# SCH_675.net
KiCad netlist of a schematic drawn in Altium Designer
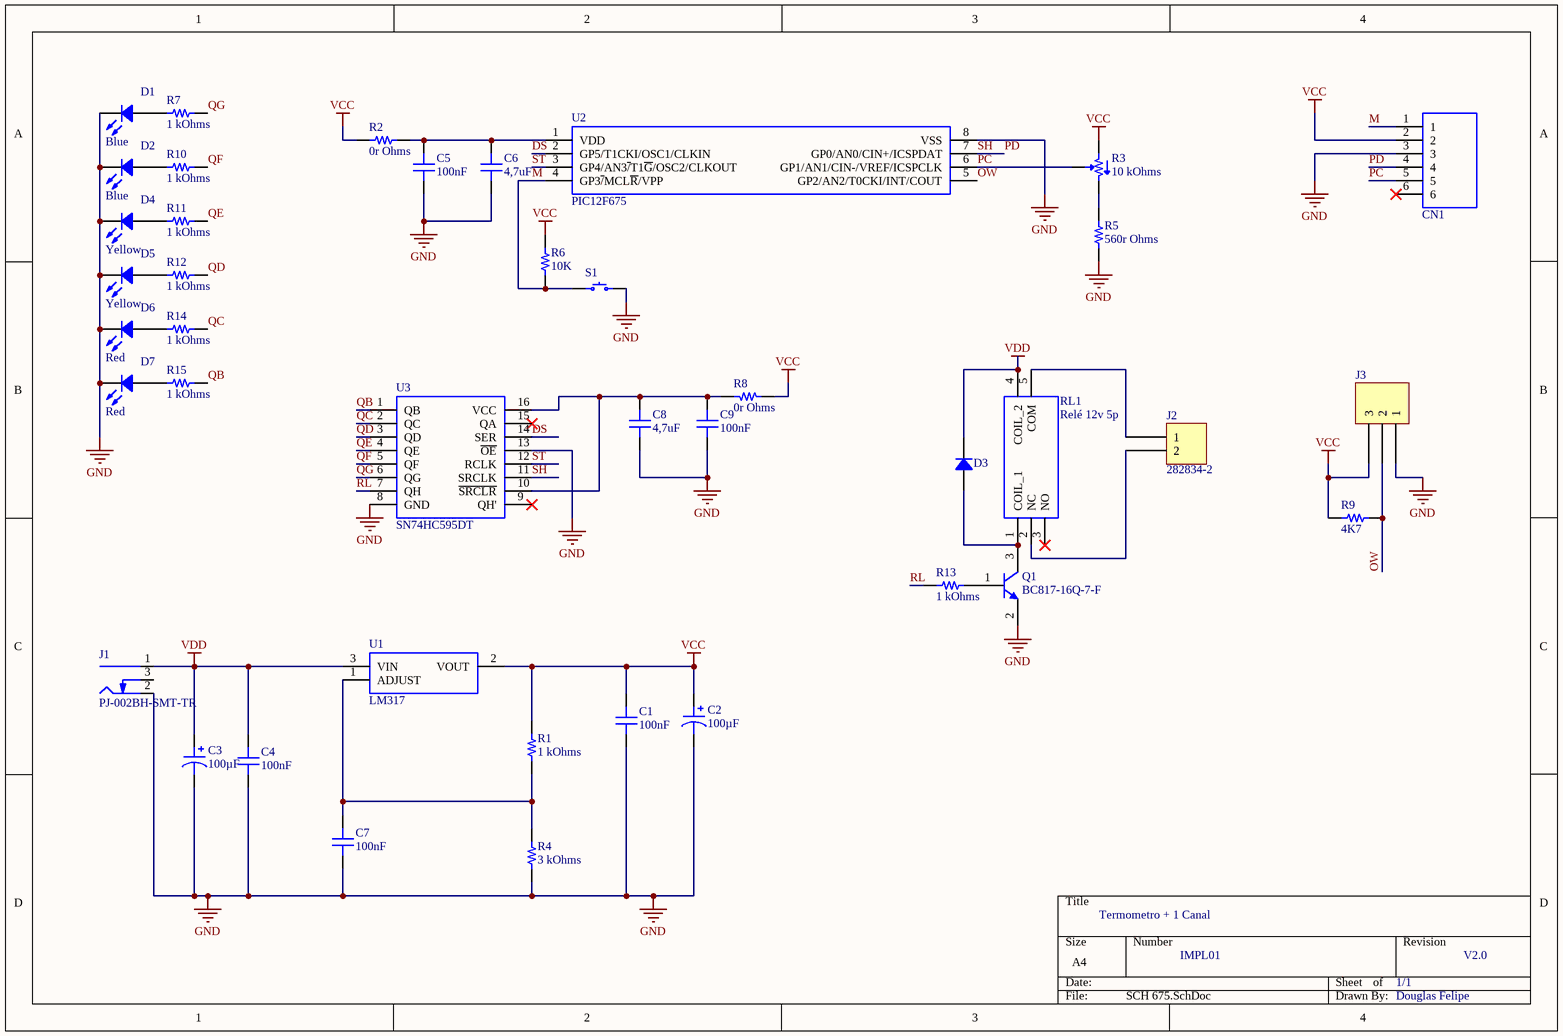
[diagram p0: SCH 675.SchDoc]

(export (version "E")
  (design (tool "Eeschema 10.0.6"))
  (components
    (comp (ref "C1")
      (value "100nF")
      (footprint "CAP 0805_2012")
      (description "CAP CER 100PF 200V C0G/NP0 0805")
      (fields (field (name "PART NUMBER") "08052A101JAT2A") (field (name "MANUFACTURER") "AVX Corporation"))
      (libsource (lib "Celestial Altium Library - altium_library") (part "Capacitor"))
    )
    (comp (ref "C2")
      (value "100µF")
      (footprint "CAP ALSMD 8.3MM H10.5MM")
      (description "CAP ALUM 22UF 20% 100V SMD")
      (fields (field (name "PART NUMBER") "100SEV22M8X10.5") (field (name "MANUFACTURER") "Rubycon"))
      (libsource (lib "Celestial Altium Library - altium_library") (part "Polarised Capacitor"))
    )
    (comp (ref "C3")
      (value "100µF")
      (footprint "CAP ALSMD 8.3MM H10.5MM")
      (description "CAP ALUM 22UF 20% 100V SMD")
      (fields (field (name "PART NUMBER") "100SEV22M8X10.5") (field (name "MANUFACTURER") "Rubycon"))
      (libsource (lib "Celestial Altium Library - altium_library") (part "Polarised Capacitor"))
    )
    (comp (ref "C4")
      (value "100nF")
      (footprint "CAP 0805_2012")
      (description "CAP CER 100PF 200V C0G/NP0 0805")
      (fields (field (name "PART NUMBER") "08052A101JAT2A") (field (name "MANUFACTURER") "AVX Corporation"))
      (libsource (lib "Celestial Altium Library - altium_library") (part "Capacitor"))
    )
    (comp (ref "C5")
      (value "100nF")
      (footprint "CAP 0805_2012")
      (description "CAP CER 100PF 200V C0G/NP0 0805")
      (fields (field (name "PART NUMBER") "08052A101JAT2A") (field (name "MANUFACTURER") "AVX Corporation"))
      (libsource (lib "Celestial Altium Library - altium_library") (part "Capacitor"))
    )
    (comp (ref "C6")
      (value "4,7uF")
      (footprint "CAP 0805_2012")
      (description "CAP CER 100PF 200V C0G/NP0 0805")
      (fields (field (name "PART NUMBER") "08052A101JAT2A") (field (name "MANUFACTURER") "AVX Corporation"))
      (libsource (lib "Celestial Altium Library - altium_library") (part "Capacitor"))
    )
    (comp (ref "C7")
      (value "100nF")
      (footprint "CAP 0805_2012")
      (description "CAP CER 100PF 200V C0G/NP0 0805")
      (fields (field (name "PART NUMBER") "08052A101JAT2A") (field (name "MANUFACTURER") "AVX Corporation"))
      (libsource (lib "Celestial Altium Library - altium_library") (part "Capacitor"))
    )
    (comp (ref "C8")
      (value "4,7uF")
      (footprint "CAP 0805_2012")
      (description "CAP CER 100PF 200V C0G/NP0 0805")
      (fields (field (name "PART NUMBER") "08052A101JAT2A") (field (name "MANUFACTURER") "AVX Corporation"))
      (libsource (lib "Celestial Altium Library - altium_library") (part "Capacitor"))
    )
    (comp (ref "C9")
      (value "100nF")
      (footprint "CAP 0805_2012")
      (description "CAP CER 100PF 200V C0G/NP0 0805")
      (fields (field (name "PART NUMBER") "08052A101JAT2A") (field (name "MANUFACTURER") "AVX Corporation"))
      (libsource (lib "Celestial Altium Library - altium_library") (part "Capacitor"))
    )
    (comp (ref "CN1")
      (value "KK 6vias")
      (footprint "KK6")
      (libsource (lib "Meus Components") (part "KK 6vias"))
    )
    (comp (ref "D1")
      (value "Blue")
      (footprint "LED 0805_2012 BLUE")
      (description "2.0(L)X1.3(W)X0.8(H) MM")
      (fields
        (field (name "PART NUMBER") "B1701NB--20D000114U1930")
        (field (name "MANUFACTURER") "Harvatek Corporation")
      )
      (libsource (lib "Celestial Altium Library - altium_library") (part "LED"))
    )
    (comp (ref "D2")
      (value "Blue")
      (footprint "LED 0805_2012 BLUE")
      (description "2.0(L)X1.3(W)X0.8(H) MM")
      (fields
        (field (name "PART NUMBER") "B1701NB--20D000114U1930")
        (field (name "MANUFACTURER") "Harvatek Corporation")
      )
      (libsource (lib "Celestial Altium Library - altium_library") (part "LED"))
    )
    (comp (ref "D3")
      (value "1N4148W-TP")
      (footprint "SOD-123")
      (description "DIODE GEN PURP 100V 150MA SOD123")
      (fields (field (name "MANUFACTURER") "Micro Commercial Co"))
      (libsource (lib "Celestial Altium Library - altium_library") (part "Diode"))
    )
    (comp (ref "D4")
      (value "Yellow")
      (footprint "LED 0805_2012 YELLOW")
      (description "LED YELLOW DIFFUSED 2SMD")
      (fields (field (name "PART NUMBER") "5975411407F") (field (name "MANUFACTURER") "Dialight"))
      (libsource (lib "Celestial Altium Library - altium_library") (part "LED"))
    )
    (comp (ref "D5")
      (value "Yellow")
      (footprint "LED 0805_2012 YELLOW")
      (description "LED YELLOW DIFFUSED 2SMD")
      (fields (field (name "PART NUMBER") "5975411407F") (field (name "MANUFACTURER") "Dialight"))
      (libsource (lib "Celestial Altium Library - altium_library") (part "LED"))
    )
    (comp (ref "D6")
      (value "Red")
      (footprint "LED 0805_2012 RED")
      (description "LED")
      (fields
        (field (name "PART NUMBER") "VFHV1112H-3BZ2B-TR")
        (field (name "MANUFACTURER") "Stanley Electric Co")
      )
      (libsource (lib "Celestial Altium Library - altium_library") (part "LED"))
    )
    (comp (ref "D7")
      (value "Red")
      (footprint "LED 0805_2012 RED")
      (description "LED")
      (fields
        (field (name "PART NUMBER") "VFHV1112H-3BZ2B-TR")
        (field (name "MANUFACTURER") "Stanley Electric Co")
      )
      (libsource (lib "Celestial Altium Library - altium_library") (part "LED"))
    )
    (comp (ref "J1")
      (value "PJ-002BH-SMT-TR")
      (footprint "CUI PJ-002BH-SMT-TR")
      (description "CONN PWR JACK 2.5X5.5MM SOLDER")
      (fields (field (name "MANUFACTURER") "CUI Devices"))
      (libsource (lib "Celestial Altium Library - altium_library") (part "Barrel Connector"))
    )
    (comp (ref "J2")
      (value "282834-2")
      (footprint "TE 282834-2")
      (description "TERM BLK 2P SIDE ENT 2.54MM PCB")
      (fields (field (name "MANUFACTURER") "TE Connectivity AMP Connectors") (field (name "VOLTAGE") "150V"))
      (libsource (lib "Celestial Altium Library - altium_library") (part "2 Pin"))
    )
    (comp (ref "J3")
      (value "0022272031")
      (footprint "MOLEX KK 0022272031")
      (description "CONN HEADER VERT 3POS 2.54MM")
      (fields (field (name "MANUFACTURER") "Molex"))
      (libsource (lib "Celestial Altium Library - altium_library") (part "3 Pin"))
    )
    (comp (ref "Q1")
      (value "BC817-16Q-7-F")
      (footprint "DIODES SOT-23-3")
      (description "TRANS NPN 45V 0.5A SOT23-3")
      (fields (field (name "MANUFACTURER") "Diodes Incorporated"))
      (libsource (lib "Celestial Altium Library - altium_library") (part "DIODES INC NPN SOT-23-3"))
    )
    (comp (ref "R1")
      (value "1 kOhms")
      (footprint "RES 0805_2012")
      (description "RES 1K OHM 0.1% 1/10W 0805")
      (fields
        (field (name "PART NUMBER") "RNCS0805BKE1K00")
        (field (name "MANUFACTURER") "Stackpole Electronics Inc")
      )
      (libsource (lib "Celestial Altium Library - altium_library") (part "Resistor"))
    )
    (comp (ref "R2")
      (value "0r Ohms")
      (footprint "RES 0805_2012")
      (description "RES 1K OHM 0.1% 1/10W 0805")
      (fields
        (field (name "PART NUMBER") "RNCS0805BKE1K00")
        (field (name "MANUFACTURER") "Stackpole Electronics Inc")
      )
      (libsource (lib "Celestial Altium Library - altium_library") (part "Resistor"))
    )
    (comp (ref "R3")
      (value "10 kOhms")
      (footprint "POT BOURNS TRIMPOT TC33")
      (description "TRIMMER 10K OHM 0.1W J LEAD TOP")
      (fields (field (name "PART NUMBER") "TC33X-1-103E") (field (name "MANUFACTURER") "Bourns Inc."))
      (libsource (lib "Celestial Altium Library - altium_library") (part "Potentiometer"))
    )
    (comp (ref "R4")
      (value "3 kOhms")
      (footprint "RES 0805_2012")
      (description "RES SMD 3K OHM 0.5% 1/8W 0805")
      (fields (field (name "PART NUMBER") "RT0805DRD073KL") (field (name "MANUFACTURER") "Yageo"))
      (libsource (lib "Celestial Altium Library - altium_library") (part "Resistor"))
    )
    (comp (ref "R5")
      (value "560r Ohms")
      (footprint "RES 0805_2012")
      (description "RES 1K OHM 0.1% 1/10W 0805")
      (fields
        (field (name "PART NUMBER") "RNCS0805BKE1K00")
        (field (name "MANUFACTURER") "Stackpole Electronics Inc")
      )
      (libsource (lib "Celestial Altium Library - altium_library") (part "Resistor"))
    )
    (comp (ref "R6")
      (value "10K")
      (footprint "RES 0805_2012")
      (description "RES 1K OHM 0.1% 1/10W 0805")
      (fields
        (field (name "PART NUMBER") "RNCS0805BKE1K00")
        (field (name "MANUFACTURER") "Stackpole Electronics Inc")
      )
      (libsource (lib "Celestial Altium Library - altium_library") (part "Resistor"))
    )
    (comp (ref "R7")
      (value "1 kOhms")
      (footprint "RES 0805_2012")
      (description "RES 1K OHM 0.1% 1/10W 0805")
      (fields
        (field (name "PART NUMBER") "RNCS0805BKE1K00")
        (field (name "MANUFACTURER") "Stackpole Electronics Inc")
      )
      (libsource (lib "Celestial Altium Library - altium_library") (part "Resistor"))
    )
    (comp (ref "R8")
      (value "0r Ohms")
      (footprint "RES 0805_2012")
      (description "RES 1K OHM 0.1% 1/10W 0805")
      (fields
        (field (name "PART NUMBER") "RNCS0805BKE1K00")
        (field (name "MANUFACTURER") "Stackpole Electronics Inc")
      )
      (libsource (lib "Celestial Altium Library - altium_library") (part "Resistor"))
    )
    (comp (ref "R9")
      (value "4K7")
      (footprint "RES 0805_2012")
      (description "RES 1K OHM 0.1% 1/10W 0805")
      (fields
        (field (name "PART NUMBER") "RNCS0805BKE1K00")
        (field (name "MANUFACTURER") "Stackpole Electronics Inc")
      )
      (libsource (lib "Celestial Altium Library - altium_library") (part "Resistor"))
    )
    (comp (ref "R10")
      (value "1 kOhms")
      (footprint "RES 0805_2012")
      (description "RES 1K OHM 0.1% 1/10W 0805")
      (fields
        (field (name "PART NUMBER") "RNCS0805BKE1K00")
        (field (name "MANUFACTURER") "Stackpole Electronics Inc")
      )
      (libsource (lib "Celestial Altium Library - altium_library") (part "Resistor"))
    )
    (comp (ref "R11")
      (value "1 kOhms")
      (footprint "RES 0805_2012")
      (description "RES 1K OHM 0.1% 1/10W 0805")
      (fields
        (field (name "PART NUMBER") "RNCS0805BKE1K00")
        (field (name "MANUFACTURER") "Stackpole Electronics Inc")
      )
      (libsource (lib "Celestial Altium Library - altium_library") (part "Resistor"))
    )
    (comp (ref "R12")
      (value "1 kOhms")
      (footprint "RES 0805_2012")
      (description "RES 1K OHM 0.1% 1/10W 0805")
      (fields
        (field (name "PART NUMBER") "RNCS0805BKE1K00")
        (field (name "MANUFACTURER") "Stackpole Electronics Inc")
      )
      (libsource (lib "Celestial Altium Library - altium_library") (part "Resistor"))
    )
    (comp (ref "R13")
      (value "1 kOhms")
      (footprint "RES 0805_2012")
      (description "RES 1K OHM 0.1% 1/10W 0805")
      (fields
        (field (name "PART NUMBER") "RNCS0805BKE1K00")
        (field (name "MANUFACTURER") "Stackpole Electronics Inc")
      )
      (libsource (lib "Celestial Altium Library - altium_library") (part "Resistor"))
    )
    (comp (ref "R14")
      (value "1 kOhms")
      (footprint "RES 0805_2012")
      (description "RES 1K OHM 0.1% 1/10W 0805")
      (fields
        (field (name "PART NUMBER") "RNCS0805BKE1K00")
        (field (name "MANUFACTURER") "Stackpole Electronics Inc")
      )
      (libsource (lib "Celestial Altium Library - altium_library") (part "Resistor"))
    )
    (comp (ref "R15")
      (value "1 kOhms")
      (footprint "RES 0805_2012")
      (description "RES 1K OHM 0.1% 1/10W 0805")
      (fields
        (field (name "PART NUMBER") "RNCS0805BKE1K00")
        (field (name "MANUFACTURER") "Stackpole Electronics Inc")
      )
      (libsource (lib "Celestial Altium Library - altium_library") (part "Resistor"))
    )
    (comp (ref "RL1")
      (value "Relé 12v 5p")
      (footprint "Relé SPDTPW")
      (libsource (lib "Meus Components") (part "Relé 12v 5p"))
    )
    (comp (ref "S1")
      (value "KXT341 LHS")
      (footprint "C&K KXT3")
      (description "SWITCH TACTILE SPST-NO 0.02A 15V")
      (fields (field (name "MANUFACTURER") "C&K"))
      (libsource (lib "Celestial Altium Library - altium_library") (part "SPST-NO 2 PIN"))
    )
    (comp (ref "U1") (value "LM317") (footprint "TO252-3") (libsource (lib "Meus Components") (part "LM317")))
    (comp (ref "U2")
      (value "PIC12F675")
      (footprint "SOIC8")
      (libsource (lib "Meus Components") (part "PIC12F675"))
    )
    (comp (ref "U3")
      (value "SN74HC595DT")
      (footprint "SOIC16")
      (libsource (lib "Meus Components") (part "SN74HC595DT"))
    )
  )
  (nets
    (net (code "1") (name "/DS") (class "Default")
      (node (ref "U2") (pin "2") (pinfunction "GP5/T1CKI/OSC1/CLKIN_2") (pintype "passive"))
      (node (ref "U3") (pin "14") (pinfunction "SER_14") (pintype "passive"))
    )
    (net (code "2") (name "/M") (class "Default")
      (node (ref "CN1") (pin "1") (pinfunction "1_1") (pintype "passive"))
      (node (ref "R6") (pin "1") (pinfunction "1_1") (pintype "passive"))
      (node (ref "S1") (pin "1") (pinfunction "1_1") (pintype "passive"))
      (node (ref "U2") (pin "4") (pinfunction "GP3~{/}MCL~{R}/VPP_4") (pintype "passive"))
    )
    (net (code "3") (name "/OW") (class "Default")
      (node (ref "J3") (pin "2") (pinfunction "2_2") (pintype "passive"))
      (node (ref "R9") (pin "1") (pinfunction "1_1") (pintype "passive"))
      (node (ref "U2") (pin "5") (pinfunction "GP2/AN2/T0CKI/INT/COUT_5") (pintype "passive"))
    )
    (net (code "4") (name "/PC") (class "Default")
      (node (ref "CN1") (pin "5") (pinfunction "5_5") (pintype "passive"))
      (node (ref "R3") (pin "2") (pinfunction "2_2") (pintype "passive"))
      (node (ref "U2") (pin "6") (pinfunction "GP1/AN1/CIN-/VREF/ICSPCLK_6") (pintype "passive"))
    )
    (net (code "5") (name "/PD") (class "Default")
      (node (ref "CN1") (pin "4") (pinfunction "4_4") (pintype "passive"))
      (node (ref "U2") (pin "7") (pinfunction "GP0/AN0/CIN+/ICSPDAT_7") (pintype "passive"))
      (node (ref "U3") (pin "11") (pinfunction "SRCLK_11") (pintype "passive"))
    )
    (net (code "6") (name "/QB") (class "Default")
      (node (ref "R15") (pin "1") (pinfunction "1_1") (pintype "passive"))
      (node (ref "U3") (pin "1") (pinfunction "QB_1") (pintype "passive"))
    )
    (net (code "7") (name "/QC") (class "Default")
      (node (ref "R14") (pin "1") (pinfunction "1_1") (pintype "passive"))
      (node (ref "U3") (pin "2") (pinfunction "QC_2") (pintype "passive"))
    )
    (net (code "8") (name "/QD") (class "Default")
      (node (ref "R12") (pin "1") (pinfunction "1_1") (pintype "passive"))
      (node (ref "U3") (pin "3") (pinfunction "QD_3") (pintype "passive"))
    )
    (net (code "9") (name "/QE") (class "Default")
      (node (ref "R11") (pin "1") (pinfunction "1_1") (pintype "passive"))
      (node (ref "U3") (pin "4") (pinfunction "QE_4") (pintype "passive"))
    )
    (net (code "10") (name "/QF") (class "Default")
      (node (ref "R10") (pin "1") (pinfunction "1_1") (pintype "passive"))
      (node (ref "U3") (pin "5") (pinfunction "QF_5") (pintype "passive"))
    )
    (net (code "11") (name "/QG") (class "Default")
      (node (ref "R7") (pin "1") (pinfunction "1_1") (pintype "passive"))
      (node (ref "U3") (pin "6") (pinfunction "QG_6") (pintype "passive"))
    )
    (net (code "12") (name "/RL") (class "Default")
      (node (ref "R13") (pin "2") (pinfunction "2_2") (pintype "passive"))
      (node (ref "U3") (pin "7") (pinfunction "QH_7") (pintype "passive"))
    )
    (net (code "13") (name "/ST") (class "Default")
      (node (ref "U2") (pin "3") (pinfunction "GP4/AN3~{/}T1~{G}/OSC2/CLKOUT_3") (pintype "passive"))
      (node (ref "U3") (pin "12") (pinfunction "RCLK_12") (pintype "passive"))
    )
    (net (code "14") (name "GND") (class "Default")
      (node (ref "C1") (pin "1") (pinfunction "1_1") (pintype "passive"))
      (node (ref "C2") (pin "2") (pinfunction "2_2") (pintype "passive"))
      (node (ref "C3") (pin "2") (pinfunction "2_2") (pintype "passive"))
      (node (ref "C4") (pin "1") (pinfunction "1_1") (pintype "passive"))
      (node (ref "C5") (pin "1") (pinfunction "1_1") (pintype "passive"))
      (node (ref "C6") (pin "1") (pinfunction "1_1") (pintype "passive"))
      (node (ref "C7") (pin "1") (pinfunction "1_1") (pintype "passive"))
      (node (ref "C8") (pin "1") (pinfunction "1_1") (pintype "passive"))
      (node (ref "C9") (pin "1") (pinfunction "1_1") (pintype "passive"))
      (node (ref "CN1") (pin "3") (pinfunction "3_3") (pintype "passive"))
      (node (ref "D1") (pin "2") (pinfunction "2_2") (pintype "passive"))
      (node (ref "D2") (pin "2") (pinfunction "2_2") (pintype "passive"))
      (node (ref "D4") (pin "2") (pinfunction "2_2") (pintype "passive"))
      (node (ref "D5") (pin "2") (pinfunction "2_2") (pintype "passive"))
      (node (ref "D6") (pin "2") (pinfunction "2_2") (pintype "passive"))
      (node (ref "D7") (pin "2") (pinfunction "2_2") (pintype "passive"))
      (node (ref "J1") (pin "2") (pinfunction "Outer_2") (pintype "passive"))
      (node (ref "J3") (pin "1") (pinfunction "1_1") (pintype "passive"))
      (node (ref "Q1") (pin "2") (pinfunction "E_2") (pintype "passive"))
      (node (ref "R4") (pin "1") (pinfunction "1_1") (pintype "passive"))
      (node (ref "R5") (pin "1") (pinfunction "1_1") (pintype "passive"))
      (node (ref "S1") (pin "2") (pinfunction "2_2") (pintype "passive"))
      (node (ref "U2") (pin "8") (pinfunction "VSS_8") (pintype "passive"))
      (node (ref "U3") (pin "13") (pinfunction "OE_13") (pintype "passive"))
      (node (ref "U3") (pin "8") (pinfunction "GND_8") (pintype "passive"))
    )
    (net (code "15") (name "Net-(D1-Pad1)") (class "Default")
      (node (ref "D1") (pin "1") (pinfunction "1_1") (pintype "passive"))
      (node (ref "R7") (pin "2") (pinfunction "2_2") (pintype "passive"))
    )
    (net (code "16") (name "Net-(D2-Pad1)") (class "Default")
      (node (ref "D2") (pin "1") (pinfunction "1_1") (pintype "passive"))
      (node (ref "R10") (pin "2") (pinfunction "2_2") (pintype "passive"))
    )
    (net (code "17") (name "Net-(D4-Pad1)") (class "Default")
      (node (ref "D4") (pin "1") (pinfunction "1_1") (pintype "passive"))
      (node (ref "R11") (pin "2") (pinfunction "2_2") (pintype "passive"))
    )
    (net (code "18") (name "Net-(D5-Pad1)") (class "Default")
      (node (ref "D5") (pin "1") (pinfunction "1_1") (pintype "passive"))
      (node (ref "R12") (pin "2") (pinfunction "2_2") (pintype "passive"))
    )
    (net (code "19") (name "Net-(D6-Pad1)") (class "Default")
      (node (ref "D6") (pin "1") (pinfunction "1_1") (pintype "passive"))
      (node (ref "R14") (pin "2") (pinfunction "2_2") (pintype "passive"))
    )
    (net (code "20") (name "Net-(D7-Pad1)") (class "Default")
      (node (ref "D7") (pin "1") (pinfunction "1_1") (pintype "passive"))
      (node (ref "R15") (pin "2") (pinfunction "2_2") (pintype "passive"))
    )
    (net (code "21") (name "Net-(Q1-B)") (class "Default")
      (node (ref "Q1") (pin "1") (pinfunction "B_1") (pintype "passive"))
      (node (ref "R13") (pin "1") (pinfunction "1_1") (pintype "passive"))
    )
    (net (code "22") (name "Net-(Q1-C)") (class "Default")
      (node (ref "D3") (pin "1") (pinfunction "1_1") (pintype "passive"))
      (node (ref "Q1") (pin "3") (pinfunction "C_3") (pintype "passive"))
      (node (ref "RL1") (pin "1") (pinfunction "COIL_1_1") (pintype "passive"))
    )
    (net (code "23") (name "Net-(R3-Pad3)") (class "Default")
      (node (ref "R3") (pin "3") (pinfunction "3_3") (pintype "passive"))
      (node (ref "R5") (pin "2") (pinfunction "2_2") (pintype "passive"))
    )
    (net (code "24") (name "Net-(RL1-COM)") (class "Default")
      (node (ref "J2") (pin "1") (pinfunction "1_1") (pintype "passive"))
      (node (ref "RL1") (pin "5") (pinfunction "COM_5") (pintype "passive"))
    )
    (net (code "25") (name "Net-(RL1-NC)") (class "Default")
      (node (ref "J2") (pin "2") (pinfunction "2_2") (pintype "passive"))
      (node (ref "RL1") (pin "2") (pinfunction "NC_2") (pintype "passive"))
    )
    (net (code "26") (name "Net-(U1-ADJUST)") (class "Default")
      (node (ref "C7") (pin "2") (pinfunction "2_2") (pintype "passive"))
      (node (ref "R1") (pin "1") (pinfunction "1_1") (pintype "passive"))
      (node (ref "R4") (pin "2") (pinfunction "2_2") (pintype "passive"))
      (node (ref "U1") (pin "1") (pinfunction "ADJUST_1") (pintype "passive"))
    )
    (net (code "27") (name "Net-(U2-VDD)") (class "Default")
      (node (ref "C5") (pin "2") (pinfunction "2_2") (pintype "passive"))
      (node (ref "C6") (pin "2") (pinfunction "2_2") (pintype "passive"))
      (node (ref "R2") (pin "1") (pinfunction "1_1") (pintype "passive"))
      (node (ref "U2") (pin "1") (pinfunction "VDD_1") (pintype "passive"))
    )
    (net (code "28") (name "Net-(U3-SRCLR)") (class "Default")
      (node (ref "C8") (pin "2") (pinfunction "2_2") (pintype "passive"))
      (node (ref "C9") (pin "2") (pinfunction "2_2") (pintype "passive"))
      (node (ref "R8") (pin "1") (pinfunction "1_1") (pintype "passive"))
      (node (ref "U3") (pin "10") (pinfunction "SRCLR_10") (pintype "passive"))
      (node (ref "U3") (pin "16") (pinfunction "VCC_16") (pintype "passive"))
    )
    (net (code "29") (name "VCC") (class "Default")
      (node (ref "C1") (pin "2") (pinfunction "2_2") (pintype "passive"))
      (node (ref "C2") (pin "1") (pinfunction "1_1") (pintype "passive"))
      (node (ref "CN1") (pin "2") (pinfunction "2_2") (pintype "passive"))
      (node (ref "J3") (pin "3") (pinfunction "3_3") (pintype "passive"))
      (node (ref "R1") (pin "2") (pinfunction "2_2") (pintype "passive"))
      (node (ref "R2") (pin "2") (pinfunction "2_2") (pintype "passive"))
      (node (ref "R3") (pin "1") (pinfunction "1_1") (pintype "passive"))
      (node (ref "R6") (pin "2") (pinfunction "2_2") (pintype "passive"))
      (node (ref "R8") (pin "2") (pinfunction "2_2") (pintype "passive"))
      (node (ref "R9") (pin "2") (pinfunction "2_2") (pintype "passive"))
      (node (ref "U1") (pin "2") (pinfunction "VOUT_2") (pintype "passive"))
    )
    (net (code "30") (name "VDD") (class "Default")
      (node (ref "C3") (pin "1") (pinfunction "1_1") (pintype "passive"))
      (node (ref "C4") (pin "2") (pinfunction "2_2") (pintype "passive"))
      (node (ref "D3") (pin "2") (pinfunction "2_2") (pintype "passive"))
      (node (ref "J1") (pin "1") (pinfunction "Centre_1") (pintype "passive"))
      (node (ref "RL1") (pin "4") (pinfunction "COIL_2_4") (pintype "passive"))
      (node (ref "U1") (pin "3") (pinfunction "VIN_3") (pintype "passive"))
    )
    (net (code "31") (name "unconnected-(CN1-Pad6)") (class "Default")
      (node (ref "CN1") (pin "6") (pinfunction "6_6") (pintype "passive+no_connect"))
    )
    (net (code "32") (name "unconnected-(J1-SW-Pad3)") (class "Default")
      (node (ref "J1") (pin "3") (pinfunction "SW_3") (pintype "passive"))
    )
    (net (code "33") (name "unconnected-(RL1-NO-Pad3)") (class "Default")
      (node (ref "RL1") (pin "3") (pinfunction "NO_3") (pintype "passive+no_connect"))
    )
    (net (code "34") (name "unconnected-(U3-QA-Pad15)") (class "Default")
      (node (ref "U3") (pin "15") (pinfunction "QA_15") (pintype "passive+no_connect"))
    )
    (net (code "35") (name "unconnected-(U3-QH'-Pad9)") (class "Default")
      (node (ref "U3") (pin "9") (pinfunction "QH'_9") (pintype "passive+no_connect"))
    )
  )
)
